# LEDMATRIX.net
KiCad netlist of a schematic drawn in Altium Designer
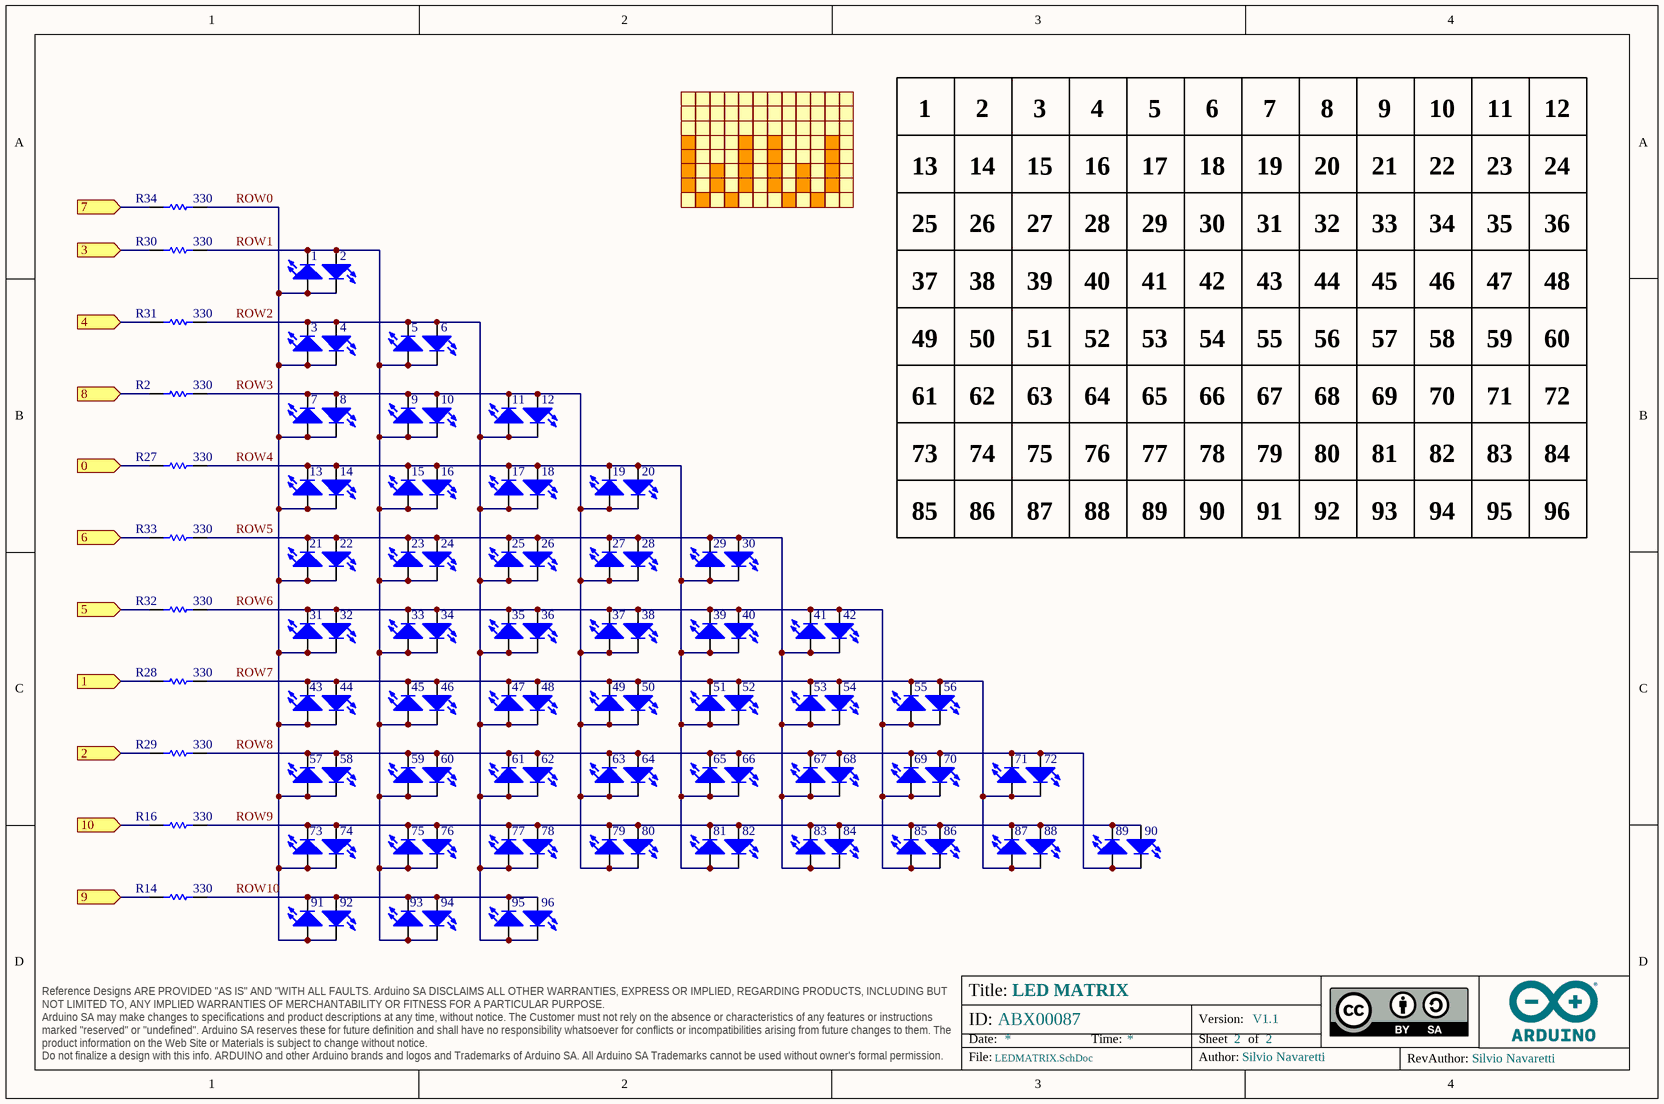
[diagram p0: LEDMATRIX.SchDoc]

(export (version "E")
  (design (tool "Eeschema 10.0.6"))
  (components
    (comp (ref "1")
      (value "XHY-STB0603SR")
      (footprint "LEDC1608X80N-AK")
      (description "LED SMD 0603 RED 625nm, water clear, 42 to 88 mcd, 120 degrees, 1.6x0.8x0.6mm")
      (fields (field (name "MANUFACTURER") "Shenzen Corehy Technology"))
      (libsource (lib "Clean") (part "LED"))
    )
    (comp (ref "2")
      (value "XHY-STB0603SR")
      (footprint "LEDC1608X80N-AK")
      (description "LED SMD 0603 RED 625nm, water clear, 42 to 88 mcd, 120 degrees, 1.6x0.8x0.6mm")
      (fields (field (name "MANUFACTURER") "Shenzen Corehy Technology"))
      (libsource (lib "Clean") (part "LED"))
    )
    (comp (ref "3")
      (value "XHY-STB0603SR")
      (footprint "LEDC1608X80N-AK")
      (description "LED SMD 0603 RED 625nm, water clear, 42 to 88 mcd, 120 degrees, 1.6x0.8x0.6mm")
      (fields (field (name "MANUFACTURER") "Shenzen Corehy Technology"))
      (libsource (lib "Clean") (part "LED"))
    )
    (comp (ref "4")
      (value "XHY-STB0603SR")
      (footprint "LEDC1608X80N-AK")
      (description "LED SMD 0603 RED 625nm, water clear, 42 to 88 mcd, 120 degrees, 1.6x0.8x0.6mm")
      (fields (field (name "MANUFACTURER") "Shenzen Corehy Technology"))
      (libsource (lib "Clean") (part "LED"))
    )
    (comp (ref "5")
      (value "XHY-STB0603SR")
      (footprint "LEDC1608X80N-AK")
      (description "LED SMD 0603 RED 625nm, water clear, 42 to 88 mcd, 120 degrees, 1.6x0.8x0.6mm")
      (fields (field (name "MANUFACTURER") "Shenzen Corehy Technology"))
      (libsource (lib "Clean") (part "LED"))
    )
    (comp (ref "6")
      (value "XHY-STB0603SR")
      (footprint "LEDC1608X80N-AK")
      (description "LED SMD 0603 RED 625nm, water clear, 42 to 88 mcd, 120 degrees, 1.6x0.8x0.6mm")
      (fields (field (name "MANUFACTURER") "Shenzen Corehy Technology"))
      (libsource (lib "Clean") (part "LED"))
    )
    (comp (ref "7")
      (value "XHY-STB0603SR")
      (footprint "LEDC1608X80N-AK")
      (description "LED SMD 0603 RED 625nm, water clear, 42 to 88 mcd, 120 degrees, 1.6x0.8x0.6mm")
      (fields (field (name "MANUFACTURER") "Shenzen Corehy Technology"))
      (libsource (lib "Clean") (part "LED"))
    )
    (comp (ref "8")
      (value "XHY-STB0603SR")
      (footprint "LEDC1608X80N-AK")
      (description "LED SMD 0603 RED 625nm, water clear, 42 to 88 mcd, 120 degrees, 1.6x0.8x0.6mm")
      (fields (field (name "MANUFACTURER") "Shenzen Corehy Technology"))
      (libsource (lib "Clean") (part "LED"))
    )
    (comp (ref "9")
      (value "XHY-STB0603SR")
      (footprint "LEDC1608X80N-AK")
      (description "LED SMD 0603 RED 625nm, water clear, 42 to 88 mcd, 120 degrees, 1.6x0.8x0.6mm")
      (fields (field (name "MANUFACTURER") "Shenzen Corehy Technology"))
      (libsource (lib "Clean") (part "LED"))
    )
    (comp (ref "10")
      (value "XHY-STB0603SR")
      (footprint "LEDC1608X80N-AK")
      (description "LED SMD 0603 RED 625nm, water clear, 42 to 88 mcd, 120 degrees, 1.6x0.8x0.6mm")
      (fields (field (name "MANUFACTURER") "Shenzen Corehy Technology"))
      (libsource (lib "Clean") (part "LED"))
    )
    (comp (ref "11")
      (value "XHY-STB0603SR")
      (footprint "LEDC1608X80N-AK")
      (description "LED SMD 0603 RED 625nm, water clear, 42 to 88 mcd, 120 degrees, 1.6x0.8x0.6mm")
      (fields (field (name "MANUFACTURER") "Shenzen Corehy Technology"))
      (libsource (lib "Clean") (part "LED"))
    )
    (comp (ref "12")
      (value "XHY-STB0603SR")
      (footprint "LEDC1608X80N-AK")
      (description "LED SMD 0603 RED 625nm, water clear, 42 to 88 mcd, 120 degrees, 1.6x0.8x0.6mm")
      (fields (field (name "MANUFACTURER") "Shenzen Corehy Technology"))
      (libsource (lib "Clean") (part "LED"))
    )
    (comp (ref "13")
      (value "XHY-STB0603SR")
      (footprint "LEDC1608X80N-AK")
      (description "LED SMD 0603 RED 625nm, water clear, 42 to 88 mcd, 120 degrees, 1.6x0.8x0.6mm")
      (fields (field (name "MANUFACTURER") "Shenzen Corehy Technology"))
      (libsource (lib "Clean") (part "LED"))
    )
    (comp (ref "14")
      (value "XHY-STB0603SR")
      (footprint "LEDC1608X80N-AK")
      (description "LED SMD 0603 RED 625nm, water clear, 42 to 88 mcd, 120 degrees, 1.6x0.8x0.6mm")
      (fields (field (name "MANUFACTURER") "Shenzen Corehy Technology"))
      (libsource (lib "Clean") (part "LED"))
    )
    (comp (ref "15")
      (value "XHY-STB0603SR")
      (footprint "LEDC1608X80N-AK")
      (description "LED SMD 0603 RED 625nm, water clear, 42 to 88 mcd, 120 degrees, 1.6x0.8x0.6mm")
      (fields (field (name "MANUFACTURER") "Shenzen Corehy Technology"))
      (libsource (lib "Clean") (part "LED"))
    )
    (comp (ref "16")
      (value "XHY-STB0603SR")
      (footprint "LEDC1608X80N-AK")
      (description "LED SMD 0603 RED 625nm, water clear, 42 to 88 mcd, 120 degrees, 1.6x0.8x0.6mm")
      (fields (field (name "MANUFACTURER") "Shenzen Corehy Technology"))
      (libsource (lib "Clean") (part "LED"))
    )
    (comp (ref "17")
      (value "XHY-STB0603SR")
      (footprint "LEDC1608X80N-AK")
      (description "LED SMD 0603 RED 625nm, water clear, 42 to 88 mcd, 120 degrees, 1.6x0.8x0.6mm")
      (fields (field (name "MANUFACTURER") "Shenzen Corehy Technology"))
      (libsource (lib "Clean") (part "LED"))
    )
    (comp (ref "18")
      (value "XHY-STB0603SR")
      (footprint "LEDC1608X80N-AK")
      (description "LED SMD 0603 RED 625nm, water clear, 42 to 88 mcd, 120 degrees, 1.6x0.8x0.6mm")
      (fields (field (name "MANUFACTURER") "Shenzen Corehy Technology"))
      (libsource (lib "Clean") (part "LED"))
    )
    (comp (ref "19")
      (value "XHY-STB0603SR")
      (footprint "LEDC1608X80N-AK")
      (description "LED SMD 0603 RED 625nm, water clear, 42 to 88 mcd, 120 degrees, 1.6x0.8x0.6mm")
      (fields (field (name "MANUFACTURER") "Shenzen Corehy Technology"))
      (libsource (lib "Clean") (part "LED"))
    )
    (comp (ref "20")
      (value "XHY-STB0603SR")
      (footprint "LEDC1608X80N-AK")
      (description "LED SMD 0603 RED 625nm, water clear, 42 to 88 mcd, 120 degrees, 1.6x0.8x0.6mm")
      (fields (field (name "MANUFACTURER") "Shenzen Corehy Technology"))
      (libsource (lib "Clean") (part "LED"))
    )
    (comp (ref "21")
      (value "XHY-STB0603SR")
      (footprint "LEDC1608X80N-AK")
      (description "LED SMD 0603 RED 625nm, water clear, 42 to 88 mcd, 120 degrees, 1.6x0.8x0.6mm")
      (fields (field (name "MANUFACTURER") "Shenzen Corehy Technology"))
      (libsource (lib "Clean") (part "LED"))
    )
    (comp (ref "22")
      (value "XHY-STB0603SR")
      (footprint "LEDC1608X80N-AK")
      (description "LED SMD 0603 RED 625nm, water clear, 42 to 88 mcd, 120 degrees, 1.6x0.8x0.6mm")
      (fields (field (name "MANUFACTURER") "Shenzen Corehy Technology"))
      (libsource (lib "Clean") (part "LED"))
    )
    (comp (ref "23")
      (value "XHY-STB0603SR")
      (footprint "LEDC1608X80N-AK")
      (description "LED SMD 0603 RED 625nm, water clear, 42 to 88 mcd, 120 degrees, 1.6x0.8x0.6mm")
      (fields (field (name "MANUFACTURER") "Shenzen Corehy Technology"))
      (libsource (lib "Clean") (part "LED"))
    )
    (comp (ref "24")
      (value "XHY-STB0603SR")
      (footprint "LEDC1608X80N-AK")
      (description "LED SMD 0603 RED 625nm, water clear, 42 to 88 mcd, 120 degrees, 1.6x0.8x0.6mm")
      (fields (field (name "MANUFACTURER") "Shenzen Corehy Technology"))
      (libsource (lib "Clean") (part "LED"))
    )
    (comp (ref "25")
      (value "XHY-STB0603SR")
      (footprint "LEDC1608X80N-AK")
      (description "LED SMD 0603 RED 625nm, water clear, 42 to 88 mcd, 120 degrees, 1.6x0.8x0.6mm")
      (fields (field (name "MANUFACTURER") "Shenzen Corehy Technology"))
      (libsource (lib "Clean") (part "LED"))
    )
    (comp (ref "26")
      (value "XHY-STB0603SR")
      (footprint "LEDC1608X80N-AK")
      (description "LED SMD 0603 RED 625nm, water clear, 42 to 88 mcd, 120 degrees, 1.6x0.8x0.6mm")
      (fields (field (name "MANUFACTURER") "Shenzen Corehy Technology"))
      (libsource (lib "Clean") (part "LED"))
    )
    (comp (ref "27")
      (value "XHY-STB0603SR")
      (footprint "LEDC1608X80N-AK")
      (description "LED SMD 0603 RED 625nm, water clear, 42 to 88 mcd, 120 degrees, 1.6x0.8x0.6mm")
      (fields (field (name "MANUFACTURER") "Shenzen Corehy Technology"))
      (libsource (lib "Clean") (part "LED"))
    )
    (comp (ref "28")
      (value "XHY-STB0603SR")
      (footprint "LEDC1608X80N-AK")
      (description "LED SMD 0603 RED 625nm, water clear, 42 to 88 mcd, 120 degrees, 1.6x0.8x0.6mm")
      (fields (field (name "MANUFACTURER") "Shenzen Corehy Technology"))
      (libsource (lib "Clean") (part "LED"))
    )
    (comp (ref "29")
      (value "XHY-STB0603SR")
      (footprint "LEDC1608X80N-AK")
      (description "LED SMD 0603 RED 625nm, water clear, 42 to 88 mcd, 120 degrees, 1.6x0.8x0.6mm")
      (fields (field (name "MANUFACTURER") "Shenzen Corehy Technology"))
      (libsource (lib "Clean") (part "LED"))
    )
    (comp (ref "30")
      (value "XHY-STB0603SR")
      (footprint "LEDC1608X80N-AK")
      (description "LED SMD 0603 RED 625nm, water clear, 42 to 88 mcd, 120 degrees, 1.6x0.8x0.6mm")
      (fields (field (name "MANUFACTURER") "Shenzen Corehy Technology"))
      (libsource (lib "Clean") (part "LED"))
    )
    (comp (ref "31")
      (value "XHY-STB0603SR")
      (footprint "LEDC1608X80N-AK")
      (description "LED SMD 0603 RED 625nm, water clear, 42 to 88 mcd, 120 degrees, 1.6x0.8x0.6mm")
      (fields (field (name "MANUFACTURER") "Shenzen Corehy Technology"))
      (libsource (lib "Clean") (part "LED"))
    )
    (comp (ref "32")
      (value "XHY-STB0603SR")
      (footprint "LEDC1608X80N-AK")
      (description "LED SMD 0603 RED 625nm, water clear, 42 to 88 mcd, 120 degrees, 1.6x0.8x0.6mm")
      (fields (field (name "MANUFACTURER") "Shenzen Corehy Technology"))
      (libsource (lib "Clean") (part "LED"))
    )
    (comp (ref "33")
      (value "XHY-STB0603SR")
      (footprint "LEDC1608X80N-AK")
      (description "LED SMD 0603 RED 625nm, water clear, 42 to 88 mcd, 120 degrees, 1.6x0.8x0.6mm")
      (fields (field (name "MANUFACTURER") "Shenzen Corehy Technology"))
      (libsource (lib "Clean") (part "LED"))
    )
    (comp (ref "34")
      (value "XHY-STB0603SR")
      (footprint "LEDC1608X80N-AK")
      (description "LED SMD 0603 RED 625nm, water clear, 42 to 88 mcd, 120 degrees, 1.6x0.8x0.6mm")
      (fields (field (name "MANUFACTURER") "Shenzen Corehy Technology"))
      (libsource (lib "Clean") (part "LED"))
    )
    (comp (ref "35")
      (value "XHY-STB0603SR")
      (footprint "LEDC1608X80N-AK")
      (description "LED SMD 0603 RED 625nm, water clear, 42 to 88 mcd, 120 degrees, 1.6x0.8x0.6mm")
      (fields (field (name "MANUFACTURER") "Shenzen Corehy Technology"))
      (libsource (lib "Clean") (part "LED"))
    )
    (comp (ref "36")
      (value "XHY-STB0603SR")
      (footprint "LEDC1608X80N-AK")
      (description "LED SMD 0603 RED 625nm, water clear, 42 to 88 mcd, 120 degrees, 1.6x0.8x0.6mm")
      (fields (field (name "MANUFACTURER") "Shenzen Corehy Technology"))
      (libsource (lib "Clean") (part "LED"))
    )
    (comp (ref "37")
      (value "XHY-STB0603SR")
      (footprint "LEDC1608X80N-AK")
      (description "LED SMD 0603 RED 625nm, water clear, 42 to 88 mcd, 120 degrees, 1.6x0.8x0.6mm")
      (fields (field (name "MANUFACTURER") "Shenzen Corehy Technology"))
      (libsource (lib "Clean") (part "LED"))
    )
    (comp (ref "38")
      (value "XHY-STB0603SR")
      (footprint "LEDC1608X80N-AK")
      (description "LED SMD 0603 RED 625nm, water clear, 42 to 88 mcd, 120 degrees, 1.6x0.8x0.6mm")
      (fields (field (name "MANUFACTURER") "Shenzen Corehy Technology"))
      (libsource (lib "Clean") (part "LED"))
    )
    (comp (ref "39")
      (value "XHY-STB0603SR")
      (footprint "LEDC1608X80N-AK")
      (description "LED SMD 0603 RED 625nm, water clear, 42 to 88 mcd, 120 degrees, 1.6x0.8x0.6mm")
      (fields (field (name "MANUFACTURER") "Shenzen Corehy Technology"))
      (libsource (lib "Clean") (part "LED"))
    )
    (comp (ref "40")
      (value "XHY-STB0603SR")
      (footprint "LEDC1608X80N-AK")
      (description "LED SMD 0603 RED 625nm, water clear, 42 to 88 mcd, 120 degrees, 1.6x0.8x0.6mm")
      (fields (field (name "MANUFACTURER") "Shenzen Corehy Technology"))
      (libsource (lib "Clean") (part "LED"))
    )
    (comp (ref "41")
      (value "XHY-STB0603SR")
      (footprint "LEDC1608X80N-AK")
      (description "LED SMD 0603 RED 625nm, water clear, 42 to 88 mcd, 120 degrees, 1.6x0.8x0.6mm")
      (fields (field (name "MANUFACTURER") "Shenzen Corehy Technology"))
      (libsource (lib "Clean") (part "LED"))
    )
    (comp (ref "42")
      (value "XHY-STB0603SR")
      (footprint "LEDC1608X80N-AK")
      (description "LED SMD 0603 RED 625nm, water clear, 42 to 88 mcd, 120 degrees, 1.6x0.8x0.6mm")
      (fields (field (name "MANUFACTURER") "Shenzen Corehy Technology"))
      (libsource (lib "Clean") (part "LED"))
    )
    (comp (ref "43")
      (value "XHY-STB0603SR")
      (footprint "LEDC1608X80N-AK")
      (description "LED SMD 0603 RED 625nm, water clear, 42 to 88 mcd, 120 degrees, 1.6x0.8x0.6mm")
      (fields (field (name "MANUFACTURER") "Shenzen Corehy Technology"))
      (libsource (lib "Clean") (part "LED"))
    )
    (comp (ref "44")
      (value "XHY-STB0603SR")
      (footprint "LEDC1608X80N-AK")
      (description "LED SMD 0603 RED 625nm, water clear, 42 to 88 mcd, 120 degrees, 1.6x0.8x0.6mm")
      (fields (field (name "MANUFACTURER") "Shenzen Corehy Technology"))
      (libsource (lib "Clean") (part "LED"))
    )
    (comp (ref "45")
      (value "XHY-STB0603SR")
      (footprint "LEDC1608X80N-AK")
      (description "LED SMD 0603 RED 625nm, water clear, 42 to 88 mcd, 120 degrees, 1.6x0.8x0.6mm")
      (fields (field (name "MANUFACTURER") "Shenzen Corehy Technology"))
      (libsource (lib "Clean") (part "LED"))
    )
    (comp (ref "46")
      (value "XHY-STB0603SR")
      (footprint "LEDC1608X80N-AK")
      (description "LED SMD 0603 RED 625nm, water clear, 42 to 88 mcd, 120 degrees, 1.6x0.8x0.6mm")
      (fields (field (name "MANUFACTURER") "Shenzen Corehy Technology"))
      (libsource (lib "Clean") (part "LED"))
    )
    (comp (ref "47")
      (value "XHY-STB0603SR")
      (footprint "LEDC1608X80N-AK")
      (description "LED SMD 0603 RED 625nm, water clear, 42 to 88 mcd, 120 degrees, 1.6x0.8x0.6mm")
      (fields (field (name "MANUFACTURER") "Shenzen Corehy Technology"))
      (libsource (lib "Clean") (part "LED"))
    )
    (comp (ref "48")
      (value "XHY-STB0603SR")
      (footprint "LEDC1608X80N-AK")
      (description "LED SMD 0603 RED 625nm, water clear, 42 to 88 mcd, 120 degrees, 1.6x0.8x0.6mm")
      (fields (field (name "MANUFACTURER") "Shenzen Corehy Technology"))
      (libsource (lib "Clean") (part "LED"))
    )
    (comp (ref "49")
      (value "XHY-STB0603SR")
      (footprint "LEDC1608X80N-AK")
      (description "LED SMD 0603 RED 625nm, water clear, 42 to 88 mcd, 120 degrees, 1.6x0.8x0.6mm")
      (fields (field (name "MANUFACTURER") "Shenzen Corehy Technology"))
      (libsource (lib "Clean") (part "LED"))
    )
    (comp (ref "50")
      (value "XHY-STB0603SR")
      (footprint "LEDC1608X80N-AK")
      (description "LED SMD 0603 RED 625nm, water clear, 42 to 88 mcd, 120 degrees, 1.6x0.8x0.6mm")
      (fields (field (name "MANUFACTURER") "Shenzen Corehy Technology"))
      (libsource (lib "Clean") (part "LED"))
    )
    (comp (ref "51")
      (value "XHY-STB0603SR")
      (footprint "LEDC1608X80N-AK")
      (description "LED SMD 0603 RED 625nm, water clear, 42 to 88 mcd, 120 degrees, 1.6x0.8x0.6mm")
      (fields (field (name "MANUFACTURER") "Shenzen Corehy Technology"))
      (libsource (lib "Clean") (part "LED"))
    )
    (comp (ref "52")
      (value "XHY-STB0603SR")
      (footprint "LEDC1608X80N-AK")
      (description "LED SMD 0603 RED 625nm, water clear, 42 to 88 mcd, 120 degrees, 1.6x0.8x0.6mm")
      (fields (field (name "MANUFACTURER") "Shenzen Corehy Technology"))
      (libsource (lib "Clean") (part "LED"))
    )
    (comp (ref "53")
      (value "XHY-STB0603SR")
      (footprint "LEDC1608X80N-AK")
      (description "LED SMD 0603 RED 625nm, water clear, 42 to 88 mcd, 120 degrees, 1.6x0.8x0.6mm")
      (fields (field (name "MANUFACTURER") "Shenzen Corehy Technology"))
      (libsource (lib "Clean") (part "LED"))
    )
    (comp (ref "54")
      (value "XHY-STB0603SR")
      (footprint "LEDC1608X80N-AK")
      (description "LED SMD 0603 RED 625nm, water clear, 42 to 88 mcd, 120 degrees, 1.6x0.8x0.6mm")
      (fields (field (name "MANUFACTURER") "Shenzen Corehy Technology"))
      (libsource (lib "Clean") (part "LED"))
    )
    (comp (ref "55")
      (value "XHY-STB0603SR")
      (footprint "LEDC1608X80N-AK")
      (description "LED SMD 0603 RED 625nm, water clear, 42 to 88 mcd, 120 degrees, 1.6x0.8x0.6mm")
      (fields (field (name "MANUFACTURER") "Shenzen Corehy Technology"))
      (libsource (lib "Clean") (part "LED"))
    )
    (comp (ref "56")
      (value "XHY-STB0603SR")
      (footprint "LEDC1608X80N-AK")
      (description "LED SMD 0603 RED 625nm, water clear, 42 to 88 mcd, 120 degrees, 1.6x0.8x0.6mm")
      (fields (field (name "MANUFACTURER") "Shenzen Corehy Technology"))
      (libsource (lib "Clean") (part "LED"))
    )
    (comp (ref "57")
      (value "XHY-STB0603SR")
      (footprint "LEDC1608X80N-AK")
      (description "LED SMD 0603 RED 625nm, water clear, 42 to 88 mcd, 120 degrees, 1.6x0.8x0.6mm")
      (fields (field (name "MANUFACTURER") "Shenzen Corehy Technology"))
      (libsource (lib "Clean") (part "LED"))
    )
    (comp (ref "58")
      (value "XHY-STB0603SR")
      (footprint "LEDC1608X80N-AK")
      (description "LED SMD 0603 RED 625nm, water clear, 42 to 88 mcd, 120 degrees, 1.6x0.8x0.6mm")
      (fields (field (name "MANUFACTURER") "Shenzen Corehy Technology"))
      (libsource (lib "Clean") (part "LED"))
    )
    (comp (ref "59")
      (value "XHY-STB0603SR")
      (footprint "LEDC1608X80N-AK")
      (description "LED SMD 0603 RED 625nm, water clear, 42 to 88 mcd, 120 degrees, 1.6x0.8x0.6mm")
      (fields (field (name "MANUFACTURER") "Shenzen Corehy Technology"))
      (libsource (lib "Clean") (part "LED"))
    )
    (comp (ref "60")
      (value "XHY-STB0603SR")
      (footprint "LEDC1608X80N-AK")
      (description "LED SMD 0603 RED 625nm, water clear, 42 to 88 mcd, 120 degrees, 1.6x0.8x0.6mm")
      (fields (field (name "MANUFACTURER") "Shenzen Corehy Technology"))
      (libsource (lib "Clean") (part "LED"))
    )
    (comp (ref "61")
      (value "XHY-STB0603SR")
      (footprint "LEDC1608X80N-AK")
      (description "LED SMD 0603 RED 625nm, water clear, 42 to 88 mcd, 120 degrees, 1.6x0.8x0.6mm")
      (fields (field (name "MANUFACTURER") "Shenzen Corehy Technology"))
      (libsource (lib "Clean") (part "LED"))
    )
    (comp (ref "62")
      (value "XHY-STB0603SR")
      (footprint "LEDC1608X80N-AK")
      (description "LED SMD 0603 RED 625nm, water clear, 42 to 88 mcd, 120 degrees, 1.6x0.8x0.6mm")
      (fields (field (name "MANUFACTURER") "Shenzen Corehy Technology"))
      (libsource (lib "Clean") (part "LED"))
    )
    (comp (ref "63")
      (value "XHY-STB0603SR")
      (footprint "LEDC1608X80N-AK")
      (description "LED SMD 0603 RED 625nm, water clear, 42 to 88 mcd, 120 degrees, 1.6x0.8x0.6mm")
      (fields (field (name "MANUFACTURER") "Shenzen Corehy Technology"))
      (libsource (lib "Clean") (part "LED"))
    )
    (comp (ref "64")
      (value "XHY-STB0603SR")
      (footprint "LEDC1608X80N-AK")
      (description "LED SMD 0603 RED 625nm, water clear, 42 to 88 mcd, 120 degrees, 1.6x0.8x0.6mm")
      (fields (field (name "MANUFACTURER") "Shenzen Corehy Technology"))
      (libsource (lib "Clean") (part "LED"))
    )
    (comp (ref "65")
      (value "XHY-STB0603SR")
      (footprint "LEDC1608X80N-AK")
      (description "LED SMD 0603 RED 625nm, water clear, 42 to 88 mcd, 120 degrees, 1.6x0.8x0.6mm")
      (fields (field (name "MANUFACTURER") "Shenzen Corehy Technology"))
      (libsource (lib "Clean") (part "LED"))
    )
    (comp (ref "66")
      (value "XHY-STB0603SR")
      (footprint "LEDC1608X80N-AK")
      (description "LED SMD 0603 RED 625nm, water clear, 42 to 88 mcd, 120 degrees, 1.6x0.8x0.6mm")
      (fields (field (name "MANUFACTURER") "Shenzen Corehy Technology"))
      (libsource (lib "Clean") (part "LED"))
    )
    (comp (ref "67")
      (value "XHY-STB0603SR")
      (footprint "LEDC1608X80N-AK")
      (description "LED SMD 0603 RED 625nm, water clear, 42 to 88 mcd, 120 degrees, 1.6x0.8x0.6mm")
      (fields (field (name "MANUFACTURER") "Shenzen Corehy Technology"))
      (libsource (lib "Clean") (part "LED"))
    )
    (comp (ref "68")
      (value "XHY-STB0603SR")
      (footprint "LEDC1608X80N-AK")
      (description "LED SMD 0603 RED 625nm, water clear, 42 to 88 mcd, 120 degrees, 1.6x0.8x0.6mm")
      (fields (field (name "MANUFACTURER") "Shenzen Corehy Technology"))
      (libsource (lib "Clean") (part "LED"))
    )
    (comp (ref "69")
      (value "XHY-STB0603SR")
      (footprint "LEDC1608X80N-AK")
      (description "LED SMD 0603 RED 625nm, water clear, 42 to 88 mcd, 120 degrees, 1.6x0.8x0.6mm")
      (fields (field (name "MANUFACTURER") "Shenzen Corehy Technology"))
      (libsource (lib "Clean") (part "LED"))
    )
    (comp (ref "70")
      (value "XHY-STB0603SR")
      (footprint "LEDC1608X80N-AK")
      (description "LED SMD 0603 RED 625nm, water clear, 42 to 88 mcd, 120 degrees, 1.6x0.8x0.6mm")
      (fields (field (name "MANUFACTURER") "Shenzen Corehy Technology"))
      (libsource (lib "Clean") (part "LED"))
    )
    (comp (ref "71")
      (value "XHY-STB0603SR")
      (footprint "LEDC1608X80N-AK")
      (description "LED SMD 0603 RED 625nm, water clear, 42 to 88 mcd, 120 degrees, 1.6x0.8x0.6mm")
      (fields (field (name "MANUFACTURER") "Shenzen Corehy Technology"))
      (libsource (lib "Clean") (part "LED"))
    )
    (comp (ref "72")
      (value "XHY-STB0603SR")
      (footprint "LEDC1608X80N-AK")
      (description "LED SMD 0603 RED 625nm, water clear, 42 to 88 mcd, 120 degrees, 1.6x0.8x0.6mm")
      (fields (field (name "MANUFACTURER") "Shenzen Corehy Technology"))
      (libsource (lib "Clean") (part "LED"))
    )
    (comp (ref "73")
      (value "XHY-STB0603SR")
      (footprint "LEDC1608X80N-AK")
      (description "LED SMD 0603 RED 625nm, water clear, 42 to 88 mcd, 120 degrees, 1.6x0.8x0.6mm")
      (fields (field (name "MANUFACTURER") "Shenzen Corehy Technology"))
      (libsource (lib "Clean") (part "LED"))
    )
    (comp (ref "74")
      (value "XHY-STB0603SR")
      (footprint "LEDC1608X80N-AK")
      (description "LED SMD 0603 RED 625nm, water clear, 42 to 88 mcd, 120 degrees, 1.6x0.8x0.6mm")
      (fields (field (name "MANUFACTURER") "Shenzen Corehy Technology"))
      (libsource (lib "Clean") (part "LED"))
    )
    (comp (ref "75")
      (value "XHY-STB0603SR")
      (footprint "LEDC1608X80N-AK")
      (description "LED SMD 0603 RED 625nm, water clear, 42 to 88 mcd, 120 degrees, 1.6x0.8x0.6mm")
      (fields (field (name "MANUFACTURER") "Shenzen Corehy Technology"))
      (libsource (lib "Clean") (part "LED"))
    )
    (comp (ref "76")
      (value "XHY-STB0603SR")
      (footprint "LEDC1608X80N-AK")
      (description "LED SMD 0603 RED 625nm, water clear, 42 to 88 mcd, 120 degrees, 1.6x0.8x0.6mm")
      (fields (field (name "MANUFACTURER") "Shenzen Corehy Technology"))
      (libsource (lib "Clean") (part "LED"))
    )
    (comp (ref "77")
      (value "XHY-STB0603SR")
      (footprint "LEDC1608X80N-AK")
      (description "LED SMD 0603 RED 625nm, water clear, 42 to 88 mcd, 120 degrees, 1.6x0.8x0.6mm")
      (fields (field (name "MANUFACTURER") "Shenzen Corehy Technology"))
      (libsource (lib "Clean") (part "LED"))
    )
    (comp (ref "78")
      (value "XHY-STB0603SR")
      (footprint "LEDC1608X80N-AK")
      (description "LED SMD 0603 RED 625nm, water clear, 42 to 88 mcd, 120 degrees, 1.6x0.8x0.6mm")
      (fields (field (name "MANUFACTURER") "Shenzen Corehy Technology"))
      (libsource (lib "Clean") (part "LED"))
    )
    (comp (ref "79")
      (value "XHY-STB0603SR")
      (footprint "LEDC1608X80N-AK")
      (description "LED SMD 0603 RED 625nm, water clear, 42 to 88 mcd, 120 degrees, 1.6x0.8x0.6mm")
      (fields (field (name "MANUFACTURER") "Shenzen Corehy Technology"))
      (libsource (lib "Clean") (part "LED"))
    )
    (comp (ref "80")
      (value "XHY-STB0603SR")
      (footprint "LEDC1608X80N-AK")
      (description "LED SMD 0603 RED 625nm, water clear, 42 to 88 mcd, 120 degrees, 1.6x0.8x0.6mm")
      (fields (field (name "MANUFACTURER") "Shenzen Corehy Technology"))
      (libsource (lib "Clean") (part "LED"))
    )
    (comp (ref "81")
      (value "XHY-STB0603SR")
      (footprint "LEDC1608X80N-AK")
      (description "LED SMD 0603 RED 625nm, water clear, 42 to 88 mcd, 120 degrees, 1.6x0.8x0.6mm")
      (fields (field (name "MANUFACTURER") "Shenzen Corehy Technology"))
      (libsource (lib "Clean") (part "LED"))
    )
    (comp (ref "82")
      (value "XHY-STB0603SR")
      (footprint "LEDC1608X80N-AK")
      (description "LED SMD 0603 RED 625nm, water clear, 42 to 88 mcd, 120 degrees, 1.6x0.8x0.6mm")
      (fields (field (name "MANUFACTURER") "Shenzen Corehy Technology"))
      (libsource (lib "Clean") (part "LED"))
    )
    (comp (ref "83")
      (value "XHY-STB0603SR")
      (footprint "LEDC1608X80N-AK")
      (description "LED SMD 0603 RED 625nm, water clear, 42 to 88 mcd, 120 degrees, 1.6x0.8x0.6mm")
      (fields (field (name "MANUFACTURER") "Shenzen Corehy Technology"))
      (libsource (lib "Clean") (part "LED"))
    )
    (comp (ref "84")
      (value "XHY-STB0603SR")
      (footprint "LEDC1608X80N-AK")
      (description "LED SMD 0603 RED 625nm, water clear, 42 to 88 mcd, 120 degrees, 1.6x0.8x0.6mm")
      (fields (field (name "MANUFACTURER") "Shenzen Corehy Technology"))
      (libsource (lib "Clean") (part "LED"))
    )
    (comp (ref "85")
      (value "XHY-STB0603SR")
      (footprint "LEDC1608X80N-AK")
      (description "LED SMD 0603 RED 625nm, water clear, 42 to 88 mcd, 120 degrees, 1.6x0.8x0.6mm")
      (fields (field (name "MANUFACTURER") "Shenzen Corehy Technology"))
      (libsource (lib "Clean") (part "LED"))
    )
    (comp (ref "86")
      (value "XHY-STB0603SR")
      (footprint "LEDC1608X80N-AK")
      (description "LED SMD 0603 RED 625nm, water clear, 42 to 88 mcd, 120 degrees, 1.6x0.8x0.6mm")
      (fields (field (name "MANUFACTURER") "Shenzen Corehy Technology"))
      (libsource (lib "Clean") (part "LED"))
    )
    (comp (ref "87")
      (value "XHY-STB0603SR")
      (footprint "LEDC1608X80N-AK")
      (description "LED SMD 0603 RED 625nm, water clear, 42 to 88 mcd, 120 degrees, 1.6x0.8x0.6mm")
      (fields (field (name "MANUFACTURER") "Shenzen Corehy Technology"))
      (libsource (lib "Clean") (part "LED"))
    )
    (comp (ref "88")
      (value "XHY-STB0603SR")
      (footprint "LEDC1608X80N-AK")
      (description "LED SMD 0603 RED 625nm, water clear, 42 to 88 mcd, 120 degrees, 1.6x0.8x0.6mm")
      (fields (field (name "MANUFACTURER") "Shenzen Corehy Technology"))
      (libsource (lib "Clean") (part "LED"))
    )
    (comp (ref "89")
      (value "XHY-STB0603SR")
      (footprint "LEDC1608X80N-AK")
      (description "LED SMD 0603 RED 625nm, water clear, 42 to 88 mcd, 120 degrees, 1.6x0.8x0.6mm")
      (fields (field (name "MANUFACTURER") "Shenzen Corehy Technology"))
      (libsource (lib "Clean") (part "LED"))
    )
    (comp (ref "90")
      (value "XHY-STB0603SR")
      (footprint "LEDC1608X80N-AK")
      (description "LED SMD 0603 RED 625nm, water clear, 42 to 88 mcd, 120 degrees, 1.6x0.8x0.6mm")
      (fields (field (name "MANUFACTURER") "Shenzen Corehy Technology"))
      (libsource (lib "Clean") (part "LED"))
    )
    (comp (ref "91")
      (value "XHY-STB0603SR")
      (footprint "LEDC1608X80N-AK")
      (description "LED SMD 0603 RED 625nm, water clear, 42 to 88 mcd, 120 degrees, 1.6x0.8x0.6mm")
      (fields (field (name "MANUFACTURER") "Shenzen Corehy Technology"))
      (libsource (lib "Clean") (part "LED"))
    )
    (comp (ref "92")
      (value "XHY-STB0603SR")
      (footprint "LEDC1608X80N-AK")
      (description "LED SMD 0603 RED 625nm, water clear, 42 to 88 mcd, 120 degrees, 1.6x0.8x0.6mm")
      (fields (field (name "MANUFACTURER") "Shenzen Corehy Technology"))
      (libsource (lib "Clean") (part "LED"))
    )
    (comp (ref "93")
      (value "XHY-STB0603SR")
      (footprint "LEDC1608X80N-AK")
      (description "LED SMD 0603 RED 625nm, water clear, 42 to 88 mcd, 120 degrees, 1.6x0.8x0.6mm")
      (fields (field (name "MANUFACTURER") "Shenzen Corehy Technology"))
      (libsource (lib "Clean") (part "LED"))
    )
    (comp (ref "94")
      (value "XHY-STB0603SR")
      (footprint "LEDC1608X80N-AK")
      (description "LED SMD 0603 RED 625nm, water clear, 42 to 88 mcd, 120 degrees, 1.6x0.8x0.6mm")
      (fields (field (name "MANUFACTURER") "Shenzen Corehy Technology"))
      (libsource (lib "Clean") (part "LED"))
    )
    (comp (ref "95")
      (value "XHY-STB0603SR")
      (footprint "LEDC1608X80N-AK")
      (description "LED SMD 0603 RED 625nm, water clear, 42 to 88 mcd, 120 degrees, 1.6x0.8x0.6mm")
      (fields (field (name "MANUFACTURER") "Shenzen Corehy Technology"))
      (libsource (lib "Clean") (part "LED"))
    )
    (comp (ref "96")
      (value "XHY-STB0603SR")
      (footprint "LEDC1608X80N-AK")
      (description "LED SMD 0603 RED 625nm, water clear, 42 to 88 mcd, 120 degrees, 1.6x0.8x0.6mm")
      (fields (field (name "MANUFACTURER") "Shenzen Corehy Technology"))
      (libsource (lib "Clean") (part "LED"))
    )
    (comp (ref "R2")
      (value "330")
      (footprint "RES-0402")
      (description "RES CHIP 0402 330R 5% 1/16W")
      (fields (field (name "PART NUMBER") "CRCW0402330RJNED") (field (name "TOLERANCE") "5%"))
      (libsource (lib "Clean") (part "RES"))
    )
    (comp (ref "R14")
      (value "330")
      (footprint "RES-0402")
      (description "RES CHIP 0402 330R 5% 1/16W")
      (fields (field (name "PART NUMBER") "CRCW0402330RJNED") (field (name "TOLERANCE") "5%"))
      (libsource (lib "Clean") (part "RES"))
    )
    (comp (ref "R16")
      (value "330")
      (footprint "RES-0402")
      (description "RES CHIP 0402 330R 5% 1/16W")
      (fields (field (name "PART NUMBER") "CRCW0402330RJNED") (field (name "TOLERANCE") "5%"))
      (libsource (lib "Clean") (part "RES"))
    )
    (comp (ref "R27")
      (value "330")
      (footprint "RES-0402")
      (description "RES CHIP 0402 330R 5% 1/16W")
      (fields (field (name "PART NUMBER") "CRCW0402330RJNED") (field (name "TOLERANCE") "5%"))
      (libsource (lib "Clean") (part "RES"))
    )
    (comp (ref "R28")
      (value "330")
      (footprint "RES-0402")
      (description "RES CHIP 0402 330R 5% 1/16W")
      (fields (field (name "PART NUMBER") "CRCW0402330RJNED") (field (name "TOLERANCE") "5%"))
      (libsource (lib "Clean") (part "RES"))
    )
    (comp (ref "R29")
      (value "330")
      (footprint "RES-0402")
      (description "RES CHIP 0402 330R 5% 1/16W")
      (fields (field (name "PART NUMBER") "CRCW0402330RJNED") (field (name "TOLERANCE") "5%"))
      (libsource (lib "Clean") (part "RES"))
    )
    (comp (ref "R30")
      (value "330")
      (footprint "RES-0402")
      (description "RES CHIP 0402 330R 5% 1/16W")
      (fields (field (name "PART NUMBER") "CRCW0402330RJNED") (field (name "TOLERANCE") "5%"))
      (libsource (lib "Clean") (part "RES"))
    )
    (comp (ref "R31")
      (value "330")
      (footprint "RES-0402")
      (description "RES CHIP 0402 330R 5% 1/16W")
      (fields (field (name "PART NUMBER") "CRCW0402330RJNED") (field (name "TOLERANCE") "5%"))
      (libsource (lib "Clean") (part "RES"))
    )
    (comp (ref "R32")
      (value "330")
      (footprint "RES-0402")
      (description "RES CHIP 0402 330R 5% 1/16W")
      (fields (field (name "PART NUMBER") "CRCW0402330RJNED") (field (name "TOLERANCE") "5%"))
      (libsource (lib "Clean") (part "RES"))
    )
    (comp (ref "R33")
      (value "330")
      (footprint "RES-0402")
      (description "RES CHIP 0402 330R 5% 1/16W")
      (fields (field (name "PART NUMBER") "CRCW0402330RJNED") (field (name "TOLERANCE") "5%"))
      (libsource (lib "Clean") (part "RES"))
    )
    (comp (ref "R34")
      (value "330")
      (footprint "RES-0402")
      (description "RES CHIP 0402 330R 5% 1/16W")
      (fields (field (name "PART NUMBER") "CRCW0402330RJNED") (field (name "TOLERANCE") "5%"))
      (libsource (lib "Clean") (part "RES"))
    )
  )
  (nets
    (net (code "1") (name "/0") (class "Default")
      (node (ref "R27") (pin "2") (pinfunction "2_2") (pintype "passive"))
    )
    (net (code "2") (name "/1") (class "Default")
      (node (ref "R28") (pin "2") (pinfunction "2_2") (pintype "passive"))
    )
    (net (code "3") (name "/2") (class "Default")
      (node (ref "R29") (pin "2") (pinfunction "2_2") (pintype "passive"))
    )
    (net (code "4") (name "/3") (class "Default")
      (node (ref "R30") (pin "2") (pinfunction "2_2") (pintype "passive"))
    )
    (net (code "5") (name "/4") (class "Default")
      (node (ref "R31") (pin "2") (pinfunction "2_2") (pintype "passive"))
    )
    (net (code "6") (name "/5") (class "Default")
      (node (ref "R32") (pin "2") (pinfunction "2_2") (pintype "passive"))
    )
    (net (code "7") (name "/6") (class "Default")
      (node (ref "R33") (pin "2") (pinfunction "2_2") (pintype "passive"))
    )
    (net (code "8") (name "/7") (class "Default")
      (node (ref "R34") (pin "2") (pinfunction "2_2") (pintype "passive"))
    )
    (net (code "9") (name "/8") (class "Default")
      (node (ref "R2") (pin "2") (pinfunction "2_2") (pintype "passive"))
    )
    (net (code "10") (name "/9") (class "Default")
      (node (ref "R14") (pin "2") (pinfunction "2_2") (pintype "passive"))
    )
    (net (code "11") (name "/10") (class "Default")
      (node (ref "R16") (pin "2") (pinfunction "2_2") (pintype "passive"))
    )
    (net (code "12") (name "/ROW0") (class "Default")
      (node (ref "1") (pin "A") (pinfunction "A_A") (pintype "passive"))
      (node (ref "13") (pin "A") (pinfunction "A_A") (pintype "passive"))
      (node (ref "14") (pin "C") (pinfunction "C_C") (pintype "passive"))
      (node (ref "2") (pin "C") (pinfunction "C_C") (pintype "passive"))
      (node (ref "21") (pin "A") (pinfunction "A_A") (pintype "passive"))
      (node (ref "22") (pin "C") (pinfunction "C_C") (pintype "passive"))
      (node (ref "3") (pin "A") (pinfunction "A_A") (pintype "passive"))
      (node (ref "31") (pin "A") (pinfunction "A_A") (pintype "passive"))
      (node (ref "32") (pin "C") (pinfunction "C_C") (pintype "passive"))
      (node (ref "4") (pin "C") (pinfunction "C_C") (pintype "passive"))
      (node (ref "43") (pin "A") (pinfunction "A_A") (pintype "passive"))
      (node (ref "44") (pin "C") (pinfunction "C_C") (pintype "passive"))
      (node (ref "57") (pin "A") (pinfunction "A_A") (pintype "passive"))
      (node (ref "58") (pin "C") (pinfunction "C_C") (pintype "passive"))
      (node (ref "7") (pin "A") (pinfunction "A_A") (pintype "passive"))
      (node (ref "73") (pin "A") (pinfunction "A_A") (pintype "passive"))
      (node (ref "74") (pin "C") (pinfunction "C_C") (pintype "passive"))
      (node (ref "8") (pin "C") (pinfunction "C_C") (pintype "passive"))
      (node (ref "91") (pin "A") (pinfunction "A_A") (pintype "passive"))
      (node (ref "92") (pin "C") (pinfunction "C_C") (pintype "passive"))
      (node (ref "R34") (pin "1") (pinfunction "1_1") (pintype "passive"))
    )
    (net (code "13") (name "/ROW1") (class "Default")
      (node (ref "1") (pin "C") (pinfunction "C_C") (pintype "passive"))
      (node (ref "10") (pin "C") (pinfunction "C_C") (pintype "passive"))
      (node (ref "15") (pin "A") (pinfunction "A_A") (pintype "passive"))
      (node (ref "16") (pin "C") (pinfunction "C_C") (pintype "passive"))
      (node (ref "2") (pin "A") (pinfunction "A_A") (pintype "passive"))
      (node (ref "23") (pin "A") (pinfunction "A_A") (pintype "passive"))
      (node (ref "24") (pin "C") (pinfunction "C_C") (pintype "passive"))
      (node (ref "33") (pin "A") (pinfunction "A_A") (pintype "passive"))
      (node (ref "34") (pin "C") (pinfunction "C_C") (pintype "passive"))
      (node (ref "45") (pin "A") (pinfunction "A_A") (pintype "passive"))
      (node (ref "46") (pin "C") (pinfunction "C_C") (pintype "passive"))
      (node (ref "5") (pin "A") (pinfunction "A_A") (pintype "passive"))
      (node (ref "59") (pin "A") (pinfunction "A_A") (pintype "passive"))
      (node (ref "6") (pin "C") (pinfunction "C_C") (pintype "passive"))
      (node (ref "60") (pin "C") (pinfunction "C_C") (pintype "passive"))
      (node (ref "75") (pin "A") (pinfunction "A_A") (pintype "passive"))
      (node (ref "76") (pin "C") (pinfunction "C_C") (pintype "passive"))
      (node (ref "9") (pin "A") (pinfunction "A_A") (pintype "passive"))
      (node (ref "93") (pin "A") (pinfunction "A_A") (pintype "passive"))
      (node (ref "94") (pin "C") (pinfunction "C_C") (pintype "passive"))
      (node (ref "R30") (pin "1") (pinfunction "1_1") (pintype "passive"))
    )
    (net (code "14") (name "/ROW2") (class "Default")
      (node (ref "11") (pin "A") (pinfunction "A_A") (pintype "passive"))
      (node (ref "12") (pin "C") (pinfunction "C_C") (pintype "passive"))
      (node (ref "17") (pin "A") (pinfunction "A_A") (pintype "passive"))
      (node (ref "18") (pin "C") (pinfunction "C_C") (pintype "passive"))
      (node (ref "25") (pin "A") (pinfunction "A_A") (pintype "passive"))
      (node (ref "26") (pin "C") (pinfunction "C_C") (pintype "passive"))
      (node (ref "3") (pin "C") (pinfunction "C_C") (pintype "passive"))
      (node (ref "35") (pin "A") (pinfunction "A_A") (pintype "passive"))
      (node (ref "36") (pin "C") (pinfunction "C_C") (pintype "passive"))
      (node (ref "4") (pin "A") (pinfunction "A_A") (pintype "passive"))
      (node (ref "47") (pin "A") (pinfunction "A_A") (pintype "passive"))
      (node (ref "48") (pin "C") (pinfunction "C_C") (pintype "passive"))
      (node (ref "5") (pin "C") (pinfunction "C_C") (pintype "passive"))
      (node (ref "6") (pin "A") (pinfunction "A_A") (pintype "passive"))
      (node (ref "61") (pin "A") (pinfunction "A_A") (pintype "passive"))
      (node (ref "62") (pin "C") (pinfunction "C_C") (pintype "passive"))
      (node (ref "77") (pin "A") (pinfunction "A_A") (pintype "passive"))
      (node (ref "78") (pin "C") (pinfunction "C_C") (pintype "passive"))
      (node (ref "95") (pin "A") (pinfunction "A_A") (pintype "passive"))
      (node (ref "96") (pin "C") (pinfunction "C_C") (pintype "passive"))
      (node (ref "R31") (pin "1") (pinfunction "1_1") (pintype "passive"))
    )
    (net (code "15") (name "/ROW3") (class "Default")
      (node (ref "10") (pin "A") (pinfunction "A_A") (pintype "passive"))
      (node (ref "11") (pin "C") (pinfunction "C_C") (pintype "passive"))
      (node (ref "12") (pin "A") (pinfunction "A_A") (pintype "passive"))
      (node (ref "19") (pin "A") (pinfunction "A_A") (pintype "passive"))
      (node (ref "20") (pin "C") (pinfunction "C_C") (pintype "passive"))
      (node (ref "27") (pin "A") (pinfunction "A_A") (pintype "passive"))
      (node (ref "28") (pin "C") (pinfunction "C_C") (pintype "passive"))
      (node (ref "37") (pin "A") (pinfunction "A_A") (pintype "passive"))
      (node (ref "38") (pin "C") (pinfunction "C_C") (pintype "passive"))
      (node (ref "49") (pin "A") (pinfunction "A_A") (pintype "passive"))
      (node (ref "50") (pin "C") (pinfunction "C_C") (pintype "passive"))
      (node (ref "63") (pin "A") (pinfunction "A_A") (pintype "passive"))
      (node (ref "64") (pin "C") (pinfunction "C_C") (pintype "passive"))
      (node (ref "7") (pin "C") (pinfunction "C_C") (pintype "passive"))
      (node (ref "79") (pin "A") (pinfunction "A_A") (pintype "passive"))
      (node (ref "8") (pin "A") (pinfunction "A_A") (pintype "passive"))
      (node (ref "80") (pin "C") (pinfunction "C_C") (pintype "passive"))
      (node (ref "9") (pin "C") (pinfunction "C_C") (pintype "passive"))
      (node (ref "R2") (pin "1") (pinfunction "1_1") (pintype "passive"))
    )
    (net (code "16") (name "/ROW4") (class "Default")
      (node (ref "13") (pin "C") (pinfunction "C_C") (pintype "passive"))
      (node (ref "14") (pin "A") (pinfunction "A_A") (pintype "passive"))
      (node (ref "15") (pin "C") (pinfunction "C_C") (pintype "passive"))
      (node (ref "16") (pin "A") (pinfunction "A_A") (pintype "passive"))
      (node (ref "17") (pin "C") (pinfunction "C_C") (pintype "passive"))
      (node (ref "18") (pin "A") (pinfunction "A_A") (pintype "passive"))
      (node (ref "19") (pin "C") (pinfunction "C_C") (pintype "passive"))
      (node (ref "20") (pin "A") (pinfunction "A_A") (pintype "passive"))
      (node (ref "29") (pin "A") (pinfunction "A_A") (pintype "passive"))
      (node (ref "30") (pin "C") (pinfunction "C_C") (pintype "passive"))
      (node (ref "39") (pin "A") (pinfunction "A_A") (pintype "passive"))
      (node (ref "40") (pin "C") (pinfunction "C_C") (pintype "passive"))
      (node (ref "51") (pin "A") (pinfunction "A_A") (pintype "passive"))
      (node (ref "52") (pin "C") (pinfunction "C_C") (pintype "passive"))
      (node (ref "65") (pin "A") (pinfunction "A_A") (pintype "passive"))
      (node (ref "66") (pin "C") (pinfunction "C_C") (pintype "passive"))
      (node (ref "81") (pin "A") (pinfunction "A_A") (pintype "passive"))
      (node (ref "82") (pin "C") (pinfunction "C_C") (pintype "passive"))
      (node (ref "R27") (pin "1") (pinfunction "1_1") (pintype "passive"))
    )
    (net (code "17") (name "/ROW5") (class "Default")
      (node (ref "21") (pin "C") (pinfunction "C_C") (pintype "passive"))
      (node (ref "22") (pin "A") (pinfunction "A_A") (pintype "passive"))
      (node (ref "23") (pin "C") (pinfunction "C_C") (pintype "passive"))
      (node (ref "24") (pin "A") (pinfunction "A_A") (pintype "passive"))
      (node (ref "25") (pin "C") (pinfunction "C_C") (pintype "passive"))
      (node (ref "26") (pin "A") (pinfunction "A_A") (pintype "passive"))
      (node (ref "27") (pin "C") (pinfunction "C_C") (pintype "passive"))
      (node (ref "28") (pin "A") (pinfunction "A_A") (pintype "passive"))
      (node (ref "29") (pin "C") (pinfunction "C_C") (pintype "passive"))
      (node (ref "30") (pin "A") (pinfunction "A_A") (pintype "passive"))
      (node (ref "41") (pin "A") (pinfunction "A_A") (pintype "passive"))
      (node (ref "42") (pin "C") (pinfunction "C_C") (pintype "passive"))
      (node (ref "53") (pin "A") (pinfunction "A_A") (pintype "passive"))
      (node (ref "54") (pin "C") (pinfunction "C_C") (pintype "passive"))
      (node (ref "67") (pin "A") (pinfunction "A_A") (pintype "passive"))
      (node (ref "68") (pin "C") (pinfunction "C_C") (pintype "passive"))
      (node (ref "83") (pin "A") (pinfunction "A_A") (pintype "passive"))
      (node (ref "84") (pin "C") (pinfunction "C_C") (pintype "passive"))
      (node (ref "R33") (pin "1") (pinfunction "1_1") (pintype "passive"))
    )
    (net (code "18") (name "/ROW6") (class "Default")
      (node (ref "31") (pin "C") (pinfunction "C_C") (pintype "passive"))
      (node (ref "32") (pin "A") (pinfunction "A_A") (pintype "passive"))
      (node (ref "33") (pin "C") (pinfunction "C_C") (pintype "passive"))
      (node (ref "34") (pin "A") (pinfunction "A_A") (pintype "passive"))
      (node (ref "35") (pin "C") (pinfunction "C_C") (pintype "passive"))
      (node (ref "36") (pin "A") (pinfunction "A_A") (pintype "passive"))
      (node (ref "37") (pin "C") (pinfunction "C_C") (pintype "passive"))
      (node (ref "38") (pin "A") (pinfunction "A_A") (pintype "passive"))
      (node (ref "39") (pin "C") (pinfunction "C_C") (pintype "passive"))
      (node (ref "40") (pin "A") (pinfunction "A_A") (pintype "passive"))
      (node (ref "41") (pin "C") (pinfunction "C_C") (pintype "passive"))
      (node (ref "42") (pin "A") (pinfunction "A_A") (pintype "passive"))
      (node (ref "55") (pin "A") (pinfunction "A_A") (pintype "passive"))
      (node (ref "56") (pin "C") (pinfunction "C_C") (pintype "passive"))
      (node (ref "69") (pin "A") (pinfunction "A_A") (pintype "passive"))
      (node (ref "70") (pin "C") (pinfunction "C_C") (pintype "passive"))
      (node (ref "85") (pin "A") (pinfunction "A_A") (pintype "passive"))
      (node (ref "86") (pin "C") (pinfunction "C_C") (pintype "passive"))
      (node (ref "R32") (pin "1") (pinfunction "1_1") (pintype "passive"))
    )
    (net (code "19") (name "/ROW7") (class "Default")
      (node (ref "43") (pin "C") (pinfunction "C_C") (pintype "passive"))
      (node (ref "44") (pin "A") (pinfunction "A_A") (pintype "passive"))
      (node (ref "45") (pin "C") (pinfunction "C_C") (pintype "passive"))
      (node (ref "46") (pin "A") (pinfunction "A_A") (pintype "passive"))
      (node (ref "47") (pin "C") (pinfunction "C_C") (pintype "passive"))
      (node (ref "48") (pin "A") (pinfunction "A_A") (pintype "passive"))
      (node (ref "49") (pin "C") (pinfunction "C_C") (pintype "passive"))
      (node (ref "50") (pin "A") (pinfunction "A_A") (pintype "passive"))
      (node (ref "51") (pin "C") (pinfunction "C_C") (pintype "passive"))
      (node (ref "52") (pin "A") (pinfunction "A_A") (pintype "passive"))
      (node (ref "53") (pin "C") (pinfunction "C_C") (pintype "passive"))
      (node (ref "54") (pin "A") (pinfunction "A_A") (pintype "passive"))
      (node (ref "55") (pin "C") (pinfunction "C_C") (pintype "passive"))
      (node (ref "56") (pin "A") (pinfunction "A_A") (pintype "passive"))
      (node (ref "71") (pin "A") (pinfunction "A_A") (pintype "passive"))
      (node (ref "72") (pin "C") (pinfunction "C_C") (pintype "passive"))
      (node (ref "87") (pin "A") (pinfunction "A_A") (pintype "passive"))
      (node (ref "88") (pin "C") (pinfunction "C_C") (pintype "passive"))
      (node (ref "R28") (pin "1") (pinfunction "1_1") (pintype "passive"))
    )
    (net (code "20") (name "/ROW8") (class "Default")
      (node (ref "57") (pin "C") (pinfunction "C_C") (pintype "passive"))
      (node (ref "58") (pin "A") (pinfunction "A_A") (pintype "passive"))
      (node (ref "59") (pin "C") (pinfunction "C_C") (pintype "passive"))
      (node (ref "60") (pin "A") (pinfunction "A_A") (pintype "passive"))
      (node (ref "61") (pin "C") (pinfunction "C_C") (pintype "passive"))
      (node (ref "62") (pin "A") (pinfunction "A_A") (pintype "passive"))
      (node (ref "63") (pin "C") (pinfunction "C_C") (pintype "passive"))
      (node (ref "64") (pin "A") (pinfunction "A_A") (pintype "passive"))
      (node (ref "65") (pin "C") (pinfunction "C_C") (pintype "passive"))
      (node (ref "66") (pin "A") (pinfunction "A_A") (pintype "passive"))
      (node (ref "67") (pin "C") (pinfunction "C_C") (pintype "passive"))
      (node (ref "68") (pin "A") (pinfunction "A_A") (pintype "passive"))
      (node (ref "69") (pin "C") (pinfunction "C_C") (pintype "passive"))
      (node (ref "70") (pin "A") (pinfunction "A_A") (pintype "passive"))
      (node (ref "71") (pin "C") (pinfunction "C_C") (pintype "passive"))
      (node (ref "72") (pin "A") (pinfunction "A_A") (pintype "passive"))
      (node (ref "89") (pin "A") (pinfunction "A_A") (pintype "passive"))
      (node (ref "90") (pin "C") (pinfunction "C_C") (pintype "passive"))
      (node (ref "R29") (pin "1") (pinfunction "1_1") (pintype "passive"))
    )
    (net (code "21") (name "/ROW9") (class "Default")
      (node (ref "73") (pin "C") (pinfunction "C_C") (pintype "passive"))
      (node (ref "74") (pin "A") (pinfunction "A_A") (pintype "passive"))
      (node (ref "75") (pin "C") (pinfunction "C_C") (pintype "passive"))
      (node (ref "76") (pin "A") (pinfunction "A_A") (pintype "passive"))
      (node (ref "77") (pin "C") (pinfunction "C_C") (pintype "passive"))
      (node (ref "78") (pin "A") (pinfunction "A_A") (pintype "passive"))
      (node (ref "79") (pin "C") (pinfunction "C_C") (pintype "passive"))
      (node (ref "80") (pin "A") (pinfunction "A_A") (pintype "passive"))
      (node (ref "81") (pin "C") (pinfunction "C_C") (pintype "passive"))
      (node (ref "82") (pin "A") (pinfunction "A_A") (pintype "passive"))
      (node (ref "83") (pin "C") (pinfunction "C_C") (pintype "passive"))
      (node (ref "84") (pin "A") (pinfunction "A_A") (pintype "passive"))
      (node (ref "85") (pin "C") (pinfunction "C_C") (pintype "passive"))
      (node (ref "86") (pin "A") (pinfunction "A_A") (pintype "passive"))
      (node (ref "87") (pin "C") (pinfunction "C_C") (pintype "passive"))
      (node (ref "88") (pin "A") (pinfunction "A_A") (pintype "passive"))
      (node (ref "89") (pin "C") (pinfunction "C_C") (pintype "passive"))
      (node (ref "90") (pin "A") (pinfunction "A_A") (pintype "passive"))
      (node (ref "R16") (pin "1") (pinfunction "1_1") (pintype "passive"))
    )
    (net (code "22") (name "/ROW10") (class "Default")
      (node (ref "91") (pin "C") (pinfunction "C_C") (pintype "passive"))
      (node (ref "92") (pin "A") (pinfunction "A_A") (pintype "passive"))
      (node (ref "93") (pin "C") (pinfunction "C_C") (pintype "passive"))
      (node (ref "94") (pin "A") (pinfunction "A_A") (pintype "passive"))
      (node (ref "95") (pin "C") (pinfunction "C_C") (pintype "passive"))
      (node (ref "96") (pin "A") (pinfunction "A_A") (pintype "passive"))
      (node (ref "R14") (pin "1") (pinfunction "1_1") (pintype "passive"))
    )
  )
)
